# PS1420P02CT_Buzzer.net
KiCad netlist of a schematic drawn in Altium Designer
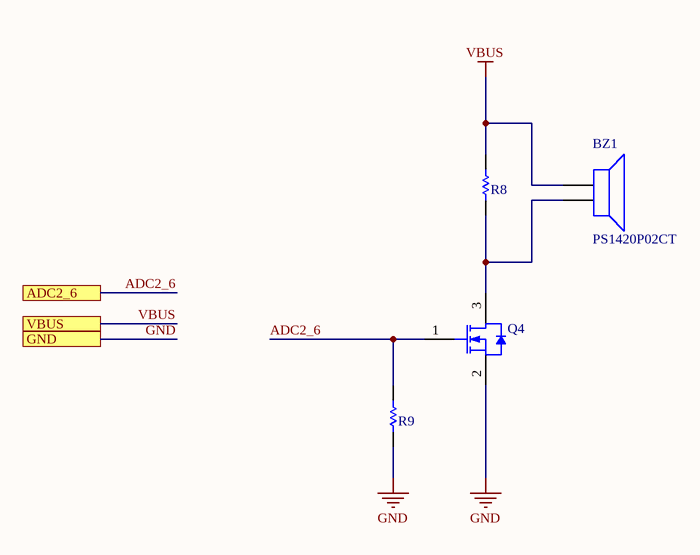
[diagram p0: PS1420P02CT_Buzzer.SchDoc]

(export (version "E")
  (design (tool "Eeschema 10.0.6"))
  (components
    (comp (ref "BZ1")
      (value "PS1420P02CT")
      (footprint "Buzz_14mm")
      (description "Buzzers Transducer, Externally Driven Piezo 5V 2kHz 70dB @ 5V, 10cm Through Hole PC Pins")
      (libsource (lib "LIB_FIT") (part "PS1420P02CT"))
    )
    (comp (ref "Q4")
      (value "BSS138-7-F")
      (footprint "DIOD-SOT23-3_V")
      (description "N-Channel Enhancement Mode Mosfet, 50 V, 0.2 A, -55 to 150 degC, 3-Pin SOT23, RoHS, Tape and Reel")
      (fields (field (name "MANUFACTURER") "Diodes Inc"))
      (libsource (lib "Altium Content Vault") (part "NEMOS-GSD-3"))
    )
    (comp (ref "R8")
      (value "ERJ-P06J102V")
      (footprint "RESC2013X70X40NL20T20")
      (description "RES SMD 1K OHM 5% 1/2W 0805")
      (fields (field (name "MANUFACTURER") "Panasonic"))
      (libsource (lib "Altium Content Vault") (part "RES"))
    )
    (comp (ref "R9")
      (value "RK73B2ATTD103J")
      (footprint "RESC2013X60X30NL20T20")
      (fields (field (name "MANUFACTURER") "KOA Speer"))
      (libsource (lib "Altium Content Vault") (part "RES"))
    )
  )
  (nets
    (net (code "1") (name "/ADC2_6") (class "Default")
      (node (ref "Q4") (pin "1") (pinfunction "G_1") (pintype "passive"))
      (node (ref "R9") (pin "1") (pinfunction "1_1") (pintype "passive"))
    )
    (net (code "2") (name "GND") (class "Default")
      (node (ref "Q4") (pin "2") (pinfunction "S_2") (pintype "passive"))
      (node (ref "R9") (pin "2") (pinfunction "2_2") (pintype "passive"))
    )
    (net (code "3") (name "Net-(Q4-D)") (class "Default")
      (node (ref "BZ1") (pin "1") (pinfunction "1_1") (pintype "passive"))
      (node (ref "Q4") (pin "3") (pinfunction "D_3") (pintype "passive"))
      (node (ref "R8") (pin "1") (pinfunction "1_1") (pintype "passive"))
    )
    (net (code "4") (name "VBUS") (class "Default")
      (node (ref "BZ1") (pin "2") (pinfunction "2_2") (pintype "passive"))
      (node (ref "R8") (pin "2") (pinfunction "2_2") (pintype "passive"))
    )
  )
)
